# 03_MAIN_POWER.net
KiCad netlist of a schematic drawn in Altium Designer
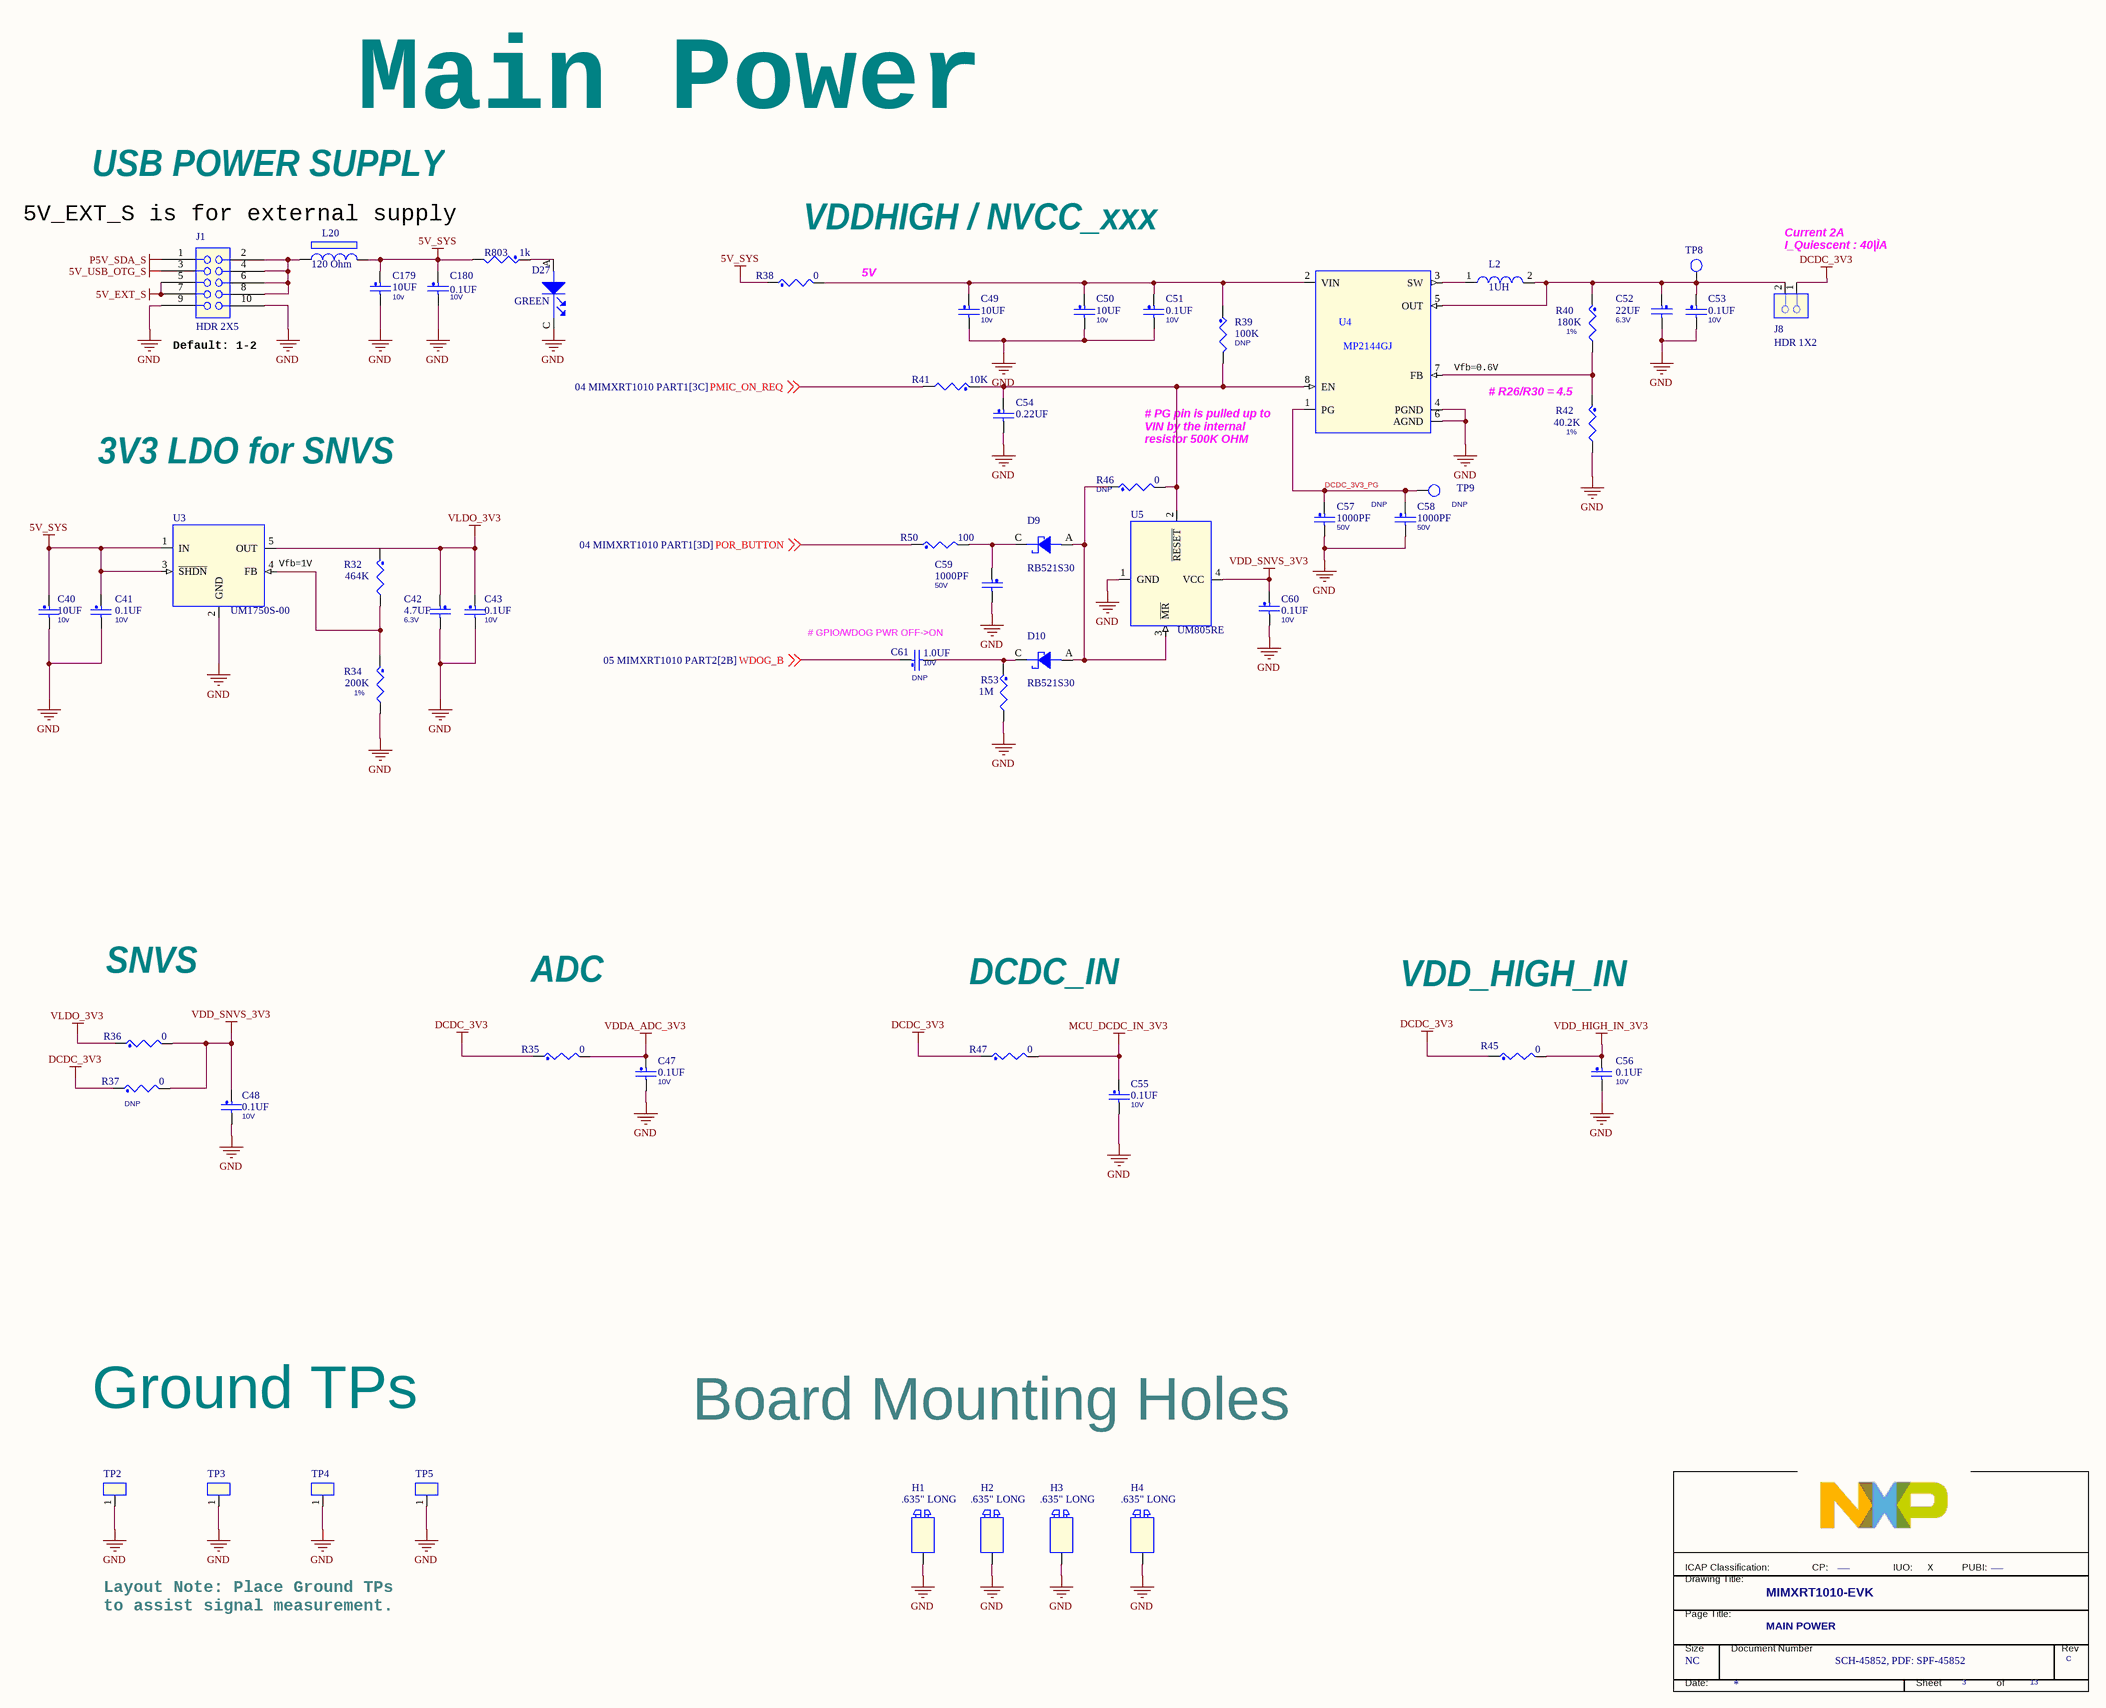
[diagram p0: 03 MAIN POWER.SchDoc]

(export (version "E")
  (design (tool "Eeschema 10.0.6"))
  (components
    (comp (ref "C40")
      (value "10UF")
      (footprint "CC0603_OV")
      (description "CAP CER 10UF 10V 10% X5R 0603")
      (fields (field (name "VOLTAGE") "10v") (field (name "TOLERANCE") "10%"))
      (libsource (lib "*") (part "CAP_NP"))
    )
    (comp (ref "C41")
      (value "0.1UF")
      (footprint "CC0402_25")
      (description "CAP CER 0.1UF 10V 10% X5R 0402")
      (fields (field (name "VOLTAGE") "10V") (field (name "TOLERANCE") "10%"))
      (libsource (lib "*") (part "CAP_NP"))
    )
    (comp (ref "C42")
      (value "4.7UF")
      (footprint "0402_CC")
      (description "CAP CER 4.7UF 6.3V 20% X5R 0402")
      (fields
        (field (name "TOLERANCE") "20%")
        (field (name "VOLTAGE RATING") "6.3V")
        (field (name "VOLTAGE") "6.3V")
      )
      (libsource (lib "*") (part "CAP_NP"))
    )
    (comp (ref "C43")
      (value "0.1UF")
      (footprint "CC0402_25")
      (description "CAP CER 0.1UF 10V 10% X5R 0402")
      (fields (field (name "VOLTAGE") "10V") (field (name "TOLERANCE") "10%"))
      (libsource (lib "*") (part "CAP_NP"))
    )
    (comp (ref "C47")
      (value "0.1UF")
      (footprint "CC0402_25")
      (description "CAP CER 0.1UF 10V 10% X5R 0402")
      (fields (field (name "VOLTAGE") "10V") (field (name "TOLERANCE") "10%"))
      (libsource (lib "*") (part "CAP_NP"))
    )
    (comp (ref "C48")
      (value "0.1UF")
      (footprint "CC0402_25")
      (description "CAP CER 0.1UF 10V 10% X5R 0402")
      (fields (field (name "VOLTAGE") "10V") (field (name "TOLERANCE") "10%"))
      (libsource (lib "*") (part "CAP_NP"))
    )
    (comp (ref "C49")
      (value "10UF")
      (footprint "CC0603_OV")
      (description "CAP CER 10UF 10V 10% X5R 0603")
      (fields (field (name "VOLTAGE") "10v") (field (name "TOLERANCE") "10%"))
      (libsource (lib "*") (part "CAP_NP"))
    )
    (comp (ref "C50")
      (value "10UF")
      (footprint "CC0603_OV")
      (description "CAP CER 10UF 10V 10% X5R 0603")
      (fields (field (name "TOLERANCE") "10%") (field (name "VOLTAGE") "10v"))
      (libsource (lib "*") (part "CAP_NP"))
    )
    (comp (ref "C51")
      (value "0.1UF")
      (footprint "CC0402_25")
      (description "CAP CER 0.1UF 10V 10% X5R 0402")
      (fields (field (name "TOLERANCE") "10%") (field (name "VOLTAGE") "10V"))
      (libsource (lib "*") (part "CAP_NP"))
    )
    (comp (ref "C52")
      (value "22UF")
      (footprint "0603_CC")
      (description "CAP CER 22UF 6.3V 20% X5R 0603")
      (fields
        (field (name "VOLTAGE RATING") "6.3V")
        (field (name "TOLERANCE") "20%")
        (field (name "VOLTAGE") "6.3V")
      )
      (libsource (lib "*") (part "CAP_NP"))
    )
    (comp (ref "C53")
      (value "0.1UF")
      (footprint "CC0402_25")
      (description "CAP CER 0.1UF 10V 10% X5R 0402")
      (fields (field (name "TOLERANCE") "10%") (field (name "VOLTAGE") "10V"))
      (libsource (lib "*") (part "CAP_NP"))
    )
    (comp (ref "C54")
      (value "0.22UF")
      (footprint "0402_CC")
      (description "CAP CER 0.22UF 6.3V 20% X5R 0402")
      (fields (field (name "TOLERANCE") "20%") (field (name "VOLTAGE") "6.3V"))
      (libsource (lib "*") (part "CAP_NP"))
    )
    (comp (ref "C55")
      (value "0.1UF")
      (footprint "CC0402_25")
      (description "CAP CER 0.1UF 10V 10% X5R 0402")
      (fields (field (name "VOLTAGE") "10V") (field (name "TOLERANCE") "10%"))
      (libsource (lib "*") (part "CAP_NP"))
    )
    (comp (ref "C56")
      (value "0.1UF")
      (footprint "CC0402_25")
      (description "CAP CER 0.1UF 10V 10% X5R 0402")
      (fields (field (name "VOLTAGE") "10V") (field (name "TOLERANCE") "10%"))
      (libsource (lib "*") (part "CAP_NP"))
    )
    (comp (ref "C57")
      (value "1000PF")
      (footprint "0402_CC")
      (description "CAP CER 1000PF 50V 5% C0G 0402")
      (fields (field (name "ASSY_OPT") "DNP") (field (name "VOLTAGE") "50V") (field (name "TOLERANCE") "5%"))
      (libsource (lib "*") (part "CAP_NP"))
    )
    (comp (ref "C58")
      (value "1000PF")
      (footprint "0402_CC")
      (description "CAP CER 1000PF 50V 5% C0G 0402")
      (fields (field (name "ASSY_OPT") "DNP") (field (name "TOLERANCE") "5%") (field (name "VOLTAGE") "50V"))
      (libsource (lib "*") (part "CAP_NP"))
    )
    (comp (ref "C59")
      (value "1000PF")
      (footprint "0402_CC")
      (description "CAP CER 1000PF 50V 5% C0G 0402")
      (fields (field (name "TOLERANCE") "5%") (field (name "VOLTAGE") "50V"))
      (libsource (lib "*") (part "CAP_NP"))
    )
    (comp (ref "C60")
      (value "0.1UF")
      (footprint "CC0402_25")
      (description "CAP CER 0.1UF 10V 10% X5R 0402")
      (fields (field (name "TOLERANCE") "10%") (field (name "VOLTAGE") "10V"))
      (libsource (lib "*") (part "CAP_NP"))
    )
    (comp (ref "C61")
      (value "1.0UF")
      (footprint "0402_cc")
      (description "CAP CER 1.0UF 10V 10% X5R 0402")
      (fields (field (name "ASSY_OPT") "DNP") (field (name "VOLTAGE") "10V"))
      (libsource (lib "*") (part "CAP_NP"))
    )
    (comp (ref "C179")
      (value "10UF")
      (footprint "CC0603_OV")
      (description "CAP CER 10UF 10V 10% X5R 0603")
      (fields (field (name "TOLERANCE") "10%") (field (name "VOLTAGE") "10v"))
      (libsource (lib "*") (part "CAP_NP"))
    )
    (comp (ref "C180")
      (value "0.1UF")
      (footprint "CC0402_25")
      (description "CAP CER 0.1UF 10V 10% X5R 0402")
      (fields (field (name "TOLERANCE") "10%") (field (name "VOLTAGE") "10V"))
      (libsource (lib "*") (part "CAP_NP"))
    )
    (comp (ref "D9")
      (value "RB521S30")
      (footprint "SOD523")
      (description "DIODE SCH RECT 200MA 30V AEC-Q101 SOD-523")
      (libsource (lib "*") (part "DIODE_SCHTKY"))
    )
    (comp (ref "D10")
      (value "RB521S30")
      (footprint "SOD523")
      (description "DIODE SCH RECT 200MA 30V AEC-Q101 SOD-523")
      (libsource (lib "*") (part "DIODE_SCHTKY"))
    )
    (comp (ref "D27")
      (value "GREEN")
      (footprint "LED_0603")
      (description "LED GRN SGL 25MA 0603")
      (libsource (lib "*") (part "LED"))
    )
    (comp (ref "H1")
      (value ".635\" LONG")
      (footprint "spacer_139t")
      (description "FASTENER, STANDOFF 4.5MMX3.53XM3.0X0.5 ROUND THR .635\"L BRASS")
      (libsource (lib "*") (part "SPACER"))
    )
    (comp (ref "H2")
      (value ".635\" LONG")
      (footprint "spacer_139t")
      (description "FASTENER, STANDOFF 4.5MMX3.53XM3.0X0.5 ROUND THR .635\"L BRASS")
      (libsource (lib "*") (part "SPACER"))
    )
    (comp (ref "H3")
      (value ".635\" LONG")
      (footprint "spacer_139t")
      (description "FASTENER, STANDOFF 4.5MMX3.53XM3.0X0.5 ROUND THR .635\"L BRASS")
      (libsource (lib "*") (part "SPACER"))
    )
    (comp (ref "H4")
      (value ".635\" LONG")
      (footprint "spacer_139t")
      (description "FASTENER, STANDOFF 4.5MMX3.53XM3.0X0.5 ROUND THR .635\"L BRASS")
      (libsource (lib "*") (part "SPACER"))
    )
    (comp (ref "J1")
      (value "HDR 2X5")
      (footprint "hdr205")
      (description "HDR 2X5 TH 100MIL CTR 338H AU 98L")
      (libsource (lib "*") (part "CONN_HDR_5X2"))
    )
    (comp (ref "J8")
      (value "HDR 1X2")
      (footprint "HDR102")
      (description "HDR 1X2 TH 100MIL SP 339H AU 98L")
      (libsource (lib "*") (part "CONN_HDR_2X1"))
    )
    (comp (ref "L2")
      (value "1UH")
      (footprint "ind_4020")
      (description "IND PWR 1UH@100KHZ 2.6A 30% SMT")
      (fields (field (name "TOLERANCE") "30%"))
      (libsource (lib "*") (part "IND"))
    )
    (comp (ref "L20")
      (value "120 Ohm")
      (footprint "0402_CC")
      (description "IND FER BEAD 120 OHM@100MHZ 0.5A 25% 0402")
      (fields (field (name "TOLERANCE") "25%"))
      (libsource (lib "*") (part "INDUCTOR_FERRITE"))
    )
    (comp (ref "R32")
      (value "464K")
      (footprint "0402_CC")
      (description "RES MF 464K 1/10W 1% AEC-Q200 0402")
      (fields (field (name "TOLERANCE") "1%"))
      (libsource (lib "*") (part "RES_Dup1"))
    )
    (comp (ref "R34")
      (value "200K")
      (footprint "0402_CC")
      (description "RES MF 200K 1/10W 1% AEC-Q200 0402")
      (fields (field (name "TOLERANCE") "1%"))
      (libsource (lib "*") (part "RES_Dup1"))
    )
    (comp (ref "R35")
      (value "0")
      (footprint "0402_CC")
      (description "RES MF ZERO OHM 1/16W 5% 0402")
      (fields (field (name "TOLERANCE") "5%"))
      (libsource (lib "*") (part "RES_Dup1"))
    )
    (comp (ref "R36")
      (value "0")
      (footprint "0402_CC")
      (description "RES MF ZERO OHM 1/16W 5% 0402")
      (fields (field (name "TOLERANCE") "5%"))
      (libsource (lib "*") (part "RES_Dup1"))
    )
    (comp (ref "R37")
      (value "0")
      (footprint "0402_CC")
      (description "RES MF ZERO OHM 1/16W 5% 0402")
      (fields (field (name "TOLERANCE") "5%") (field (name "ASSY_OPT") "DNP"))
      (libsource (lib "*") (part "RES_Dup1"))
    )
    (comp (ref "R38")
      (value "0")
      (footprint "0402_CC")
      (description "RES MF ZERO OHM 1/16W 5% 0402")
      (fields (field (name "TOLERANCE") "5%"))
      (libsource (lib "*") (part "RES_Dup1"))
    )
    (comp (ref "R39")
      (value "100K")
      (footprint "0402_CC")
      (description "RES MF 100K 1/16W 5% 0402")
      (fields (field (name "ASSY_OPT") "DNP") (field (name "TOLERANCE") "5%"))
      (libsource (lib "*") (part "RES_Dup1"))
    )
    (comp (ref "R40")
      (value "180K")
      (footprint "0402_CC")
      (description "RES MF 180K 1/10W 1% AEC-Q200 0402")
      (fields (field (name "TOLERANCE") "1%"))
      (libsource (lib "*") (part "RES_Dup1"))
    )
    (comp (ref "R41")
      (value "10K")
      (footprint "0402_CC")
      (description "RES MF 10K 1/16W 5% 0402")
      (fields (field (name "TOLERANCE") "5%"))
      (libsource (lib "*") (part "RES_Dup1"))
    )
    (comp (ref "R42")
      (value "40.2K")
      (footprint "0402_CC")
      (description "RES MF 40.2K  1/16W 1% 0402")
      (fields (field (name "TOLERANCE") "1%"))
      (libsource (lib "*") (part "RES_Dup1"))
    )
    (comp (ref "R45")
      (value "0")
      (footprint "0402_CC")
      (description "RES MF ZERO OHM 1/16W 5% 0402")
      (fields (field (name "TOLERANCE") "5%"))
      (libsource (lib "*") (part "RES_Dup1"))
    )
    (comp (ref "R46")
      (value "0")
      (footprint "0402_CC")
      (description "RES MF ZERO OHM 1/16W 5% 0402")
      (fields (field (name "TOLERANCE") "5%") (field (name "ASSY_OPT") "DNP"))
      (libsource (lib "*") (part "RES_Dup1"))
    )
    (comp (ref "R47")
      (value "0")
      (footprint "0402_CC")
      (description "RES MF ZERO OHM 1/16W 5% 0402")
      (fields (field (name "TOLERANCE") "5%"))
      (libsource (lib "*") (part "RES_Dup1"))
    )
    (comp (ref "R50")
      (value "100")
      (footprint "0402_CC")
      (description "RES MF 100 OHM 1/16W 1% 0402")
      (fields (field (name "TOLERANCE") "1%"))
      (libsource (lib "*") (part "RES_Dup1"))
    )
    (comp (ref "R53")
      (value "1M")
      (footprint "0402_CC")
      (description "RES MF 1M 1/10W 5% AEC-Q200 0402")
      (fields (field (name "TOLERANCE") "5%"))
      (libsource (lib "*") (part "RES_Dup1"))
    )
    (comp (ref "R803")
      (value "1k")
      (footprint "0402_CC")
      (description "RES MF 1.0K 1/16W 5% 0402")
      (fields (field (name "TOLERANCE") "5%"))
      (libsource (lib "*") (part "RES_Dup1"))
    )
    (comp (ref "TP2")
      (value "5006")
      (footprint "tp_th_063")
      (description "TEST POINT BLK 70X220 MIL TH")
      (libsource (lib "*") (part "TEST_POINT"))
    )
    (comp (ref "TP3")
      (value "5006")
      (footprint "tp_th_063")
      (description "TEST POINT BLK 70X220 MIL TH")
      (libsource (lib "*") (part "TEST_POINT"))
    )
    (comp (ref "TP4")
      (value "5006")
      (footprint "tp_th_063")
      (description "TEST POINT BLK 70X220 MIL TH")
      (libsource (lib "*") (part "TEST_POINT"))
    )
    (comp (ref "TP5")
      (value "5006")
      (footprint "tp_th_063")
      (description "TEST POINT BLK 70X220 MIL TH")
      (libsource (lib "*") (part "TEST_POINT"))
    )
    (comp (ref "TP8")
      (value "TP_35MIL")
      (footprint "testpoint_35mil")
      (description "TEST POINT PAD .035 SMT, no part to order")
      (libsource (lib "*") (part "T POINT R"))
    )
    (comp (ref "TP9")
      (value "TP_35MIL")
      (footprint "testpoint_35mil")
      (description "TEST POINT PAD .035 SMT, no part to order")
      (libsource (lib "*") (part "T POINT R"))
    )
    (comp (ref "U3")
      (value "UM1750S-00")
      (footprint "sot23-5_a")
      (description "IC VREG LDO ADJ 1-5V 350mA 2.5-6V SOT23-5")
      (libsource (lib "*") (part "UM1750S-00_5P"))
    )
    (comp (ref "U4")
      (value "MP2144GJ")
      (footprint "tsot23_8_0p65_2x1")
      (description "IC SYNC STEP-DOWN SW 1.2MHZ 0.6V 2A 2.5-5.5V TSOT23-8")
      (libsource (lib "*") (part "MP2144GJ_TSOT23_8P"))
    )
    (comp (ref "U5")
      (value "UM805RE")
      (footprint "sot_143")
      (description "IC VOLT MONITOR 2.63V VTH RST 1-5.5V SOT143")
      (libsource (lib "*") (part "UM805_4P"))
    )
  )
  (nets
    (net (code "1") (name "/DCDC_3V3_PG") (class "Default")
      (node (ref "C57") (pin "1") (pinfunction "1_1") (pintype "passive"))
      (node (ref "C58") (pin "1") (pinfunction "1_1") (pintype "passive"))
      (node (ref "TP9") (pin "1") (pinfunction "TP_1") (pintype "passive"))
      (node (ref "U4") (pin "1") (pinfunction "PG_1") (pintype "open_collector"))
    )
    (net (code "2") (name "5V_EXT_S") (class "Default")
      (node (ref "J1") (pin "5") (pinfunction "A3_5") (pintype "passive"))
      (node (ref "J1") (pin "7") (pinfunction "A4_7") (pintype "passive"))
    )
    (net (code "3") (name "5V_SYS") (class "Default")
      (node (ref "C179") (pin "1") (pinfunction "1_1") (pintype "passive"))
      (node (ref "C180") (pin "1") (pinfunction "1_1") (pintype "passive"))
      (node (ref "C40") (pin "1") (pinfunction "1_1") (pintype "passive"))
      (node (ref "C41") (pin "1") (pinfunction "1_1") (pintype "passive"))
      (node (ref "L20") (pin "2") (pinfunction "2_2") (pintype "passive"))
      (node (ref "R38") (pin "1") (pinfunction "1_1") (pintype "passive"))
      (node (ref "R803") (pin "2") (pinfunction "2_2") (pintype "passive"))
      (node (ref "U3") (pin "1") (pinfunction "IN_1") (pintype "power_in"))
      (node (ref "U3") (pin "3") (pinfunction "~{SHDN}_3") (pintype "input"))
    )
    (net (code "4") (name "5V_USB_OTG_S") (class "Default")
      (node (ref "J1") (pin "3") (pinfunction "A2_3") (pintype "passive"))
    )
    (net (code "5") (name "DCDC_3V3") (class "Default")
      (node (ref "J8") (pin "1") (pinfunction "1_1") (pintype "passive"))
      (node (ref "R35") (pin "1") (pinfunction "1_1") (pintype "passive"))
      (node (ref "R37") (pin "1") (pinfunction "1_1") (pintype "passive"))
      (node (ref "R45") (pin "1") (pinfunction "1_1") (pintype "passive"))
      (node (ref "R47") (pin "1") (pinfunction "1_1") (pintype "passive"))
    )
    (net (code "6") (name "GND") (class "Default")
      (node (ref "C179") (pin "2") (pinfunction "2_2") (pintype "passive"))
      (node (ref "C180") (pin "2") (pinfunction "2_2") (pintype "passive"))
      (node (ref "C40") (pin "2") (pinfunction "2_2") (pintype "passive"))
      (node (ref "C41") (pin "2") (pinfunction "2_2") (pintype "passive"))
      (node (ref "C42") (pin "2") (pinfunction "2_2") (pintype "passive"))
      (node (ref "C43") (pin "2") (pinfunction "2_2") (pintype "passive"))
      (node (ref "C47") (pin "2") (pinfunction "2_2") (pintype "passive"))
      (node (ref "C48") (pin "2") (pinfunction "2_2") (pintype "passive"))
      (node (ref "C49") (pin "2") (pinfunction "2_2") (pintype "passive"))
      (node (ref "C50") (pin "2") (pinfunction "2_2") (pintype "passive"))
      (node (ref "C51") (pin "2") (pinfunction "2_2") (pintype "passive"))
      (node (ref "C52") (pin "2") (pinfunction "2_2") (pintype "passive"))
      (node (ref "C53") (pin "2") (pinfunction "2_2") (pintype "passive"))
      (node (ref "C54") (pin "2") (pinfunction "2_2") (pintype "passive"))
      (node (ref "C55") (pin "2") (pinfunction "2_2") (pintype "passive"))
      (node (ref "C56") (pin "2") (pinfunction "2_2") (pintype "passive"))
      (node (ref "C57") (pin "2") (pinfunction "2_2") (pintype "passive"))
      (node (ref "C58") (pin "2") (pinfunction "2_2") (pintype "passive"))
      (node (ref "C59") (pin "2") (pinfunction "2_2") (pintype "passive"))
      (node (ref "C60") (pin "2") (pinfunction "2_2") (pintype "passive"))
      (node (ref "D27") (pin "C") (pinfunction "CATHODE_C") (pintype "passive"))
      (node (ref "H1") (pin "1") (pinfunction "NC_1_1") (pintype "passive"))
      (node (ref "H2") (pin "1") (pinfunction "NC_1_1") (pintype "passive"))
      (node (ref "H3") (pin "1") (pinfunction "NC_1_1") (pintype "passive"))
      (node (ref "H4") (pin "1") (pinfunction "NC_1_1") (pintype "passive"))
      (node (ref "J1") (pin "10") (pinfunction "B5_10") (pintype "passive"))
      (node (ref "J1") (pin "9") (pinfunction "A5_9") (pintype "passive"))
      (node (ref "R34") (pin "2") (pinfunction "2_2") (pintype "passive"))
      (node (ref "R42") (pin "2") (pinfunction "2_2") (pintype "passive"))
      (node (ref "R53") (pin "2") (pinfunction "2_2") (pintype "passive"))
      (node (ref "TP2") (pin "1") (pinfunction "1_1") (pintype "passive"))
      (node (ref "TP3") (pin "1") (pinfunction "1_1") (pintype "passive"))
      (node (ref "TP4") (pin "1") (pinfunction "1_1") (pintype "passive"))
      (node (ref "TP5") (pin "1") (pinfunction "1_1") (pintype "passive"))
      (node (ref "U3") (pin "2") (pinfunction "GND_2") (pintype "power_in"))
      (node (ref "U4") (pin "4") (pinfunction "PGND_4") (pintype "power_in"))
      (node (ref "U4") (pin "6") (pinfunction "AGND_6") (pintype "power_in"))
      (node (ref "U5") (pin "1") (pinfunction "GND_1") (pintype "power_in"))
    )
    (net (code "7") (name "MCU_DCDC_IN_3V3") (class "Default")
      (node (ref "C55") (pin "1") (pinfunction "1_1") (pintype "passive"))
      (node (ref "R47") (pin "2") (pinfunction "2_2") (pintype "passive"))
    )
    (net (code "8") (name "Net-(C59-Pad1)") (class "Default")
      (node (ref "C59") (pin "1") (pinfunction "1_1") (pintype "passive"))
      (node (ref "D9") (pin "C") (pinfunction "C_C") (pintype "passive"))
      (node (ref "R50") (pin "2") (pinfunction "2_2") (pintype "passive"))
    )
    (net (code "9") (name "Net-(C61-Pad2)") (class "Default")
      (node (ref "C61") (pin "2") (pinfunction "2_2") (pintype "passive"))
      (node (ref "D10") (pin "C") (pinfunction "C_C") (pintype "passive"))
      (node (ref "R53") (pin "1") (pinfunction "1_1") (pintype "passive"))
    )
    (net (code "10") (name "Net-(D27-ANODE)") (class "Default")
      (node (ref "D27") (pin "A") (pinfunction "ANODE_A") (pintype "passive"))
      (node (ref "R803") (pin "1") (pinfunction "1_1") (pintype "passive"))
    )
    (net (code "11") (name "Net-(J1-B1)") (class "Default")
      (node (ref "J1") (pin "2") (pinfunction "B1_2") (pintype "passive"))
      (node (ref "J1") (pin "4") (pinfunction "B2_4") (pintype "passive"))
      (node (ref "J1") (pin "6") (pinfunction "B3_6") (pintype "passive"))
      (node (ref "J1") (pin "8") (pinfunction "B4_8") (pintype "passive"))
      (node (ref "L20") (pin "1") (pinfunction "1_1") (pintype "passive"))
    )
    (net (code "12") (name "Net-(TP8-TP)") (class "Default")
      (node (ref "C52") (pin "1") (pinfunction "1_1") (pintype "passive"))
      (node (ref "C53") (pin "1") (pinfunction "1_1") (pintype "passive"))
      (node (ref "J8") (pin "2") (pinfunction "2_2") (pintype "passive"))
      (node (ref "L2") (pin "2") (pinfunction "2_2") (pintype "passive"))
      (node (ref "R40") (pin "1") (pinfunction "1_1") (pintype "passive"))
      (node (ref "TP8") (pin "1") (pinfunction "TP_1") (pintype "passive"))
      (node (ref "U4") (pin "5") (pinfunction "OUT_5") (pintype "input"))
    )
    (net (code "13") (name "Net-(U3-FB)") (class "Default")
      (node (ref "R32") (pin "2") (pinfunction "2_2") (pintype "passive"))
      (node (ref "R34") (pin "1") (pinfunction "1_1") (pintype "passive"))
      (node (ref "U3") (pin "4") (pinfunction "FB_4") (pintype "input"))
    )
    (net (code "14") (name "Net-(U4-EN)") (class "Default")
      (node (ref "C54") (pin "1") (pinfunction "1_1") (pintype "passive"))
      (node (ref "R39") (pin "2") (pinfunction "2_2") (pintype "passive"))
      (node (ref "R41") (pin "1") (pinfunction "1_1") (pintype "passive"))
      (node (ref "R46") (pin "2") (pinfunction "2_2") (pintype "passive"))
      (node (ref "U4") (pin "8") (pinfunction "EN_8") (pintype "input"))
      (node (ref "U5") (pin "2") (pinfunction "~{RESET}_2") (pintype "open_collector"))
    )
    (net (code "15") (name "Net-(U4-FB)") (class "Default")
      (node (ref "R40") (pin "2") (pinfunction "2_2") (pintype "passive"))
      (node (ref "R42") (pin "1") (pinfunction "1_1") (pintype "passive"))
      (node (ref "U4") (pin "7") (pinfunction "FB_7") (pintype "input"))
    )
    (net (code "16") (name "Net-(U4-SW)") (class "Default")
      (node (ref "L2") (pin "1") (pinfunction "1_1") (pintype "passive"))
      (node (ref "U4") (pin "3") (pinfunction "SW_3") (pintype "output"))
    )
    (net (code "17") (name "Net-(U4-VIN)") (class "Default")
      (node (ref "C49") (pin "1") (pinfunction "1_1") (pintype "passive"))
      (node (ref "C50") (pin "1") (pinfunction "1_1") (pintype "passive"))
      (node (ref "C51") (pin "1") (pinfunction "1_1") (pintype "passive"))
      (node (ref "R38") (pin "2") (pinfunction "2_2") (pintype "passive"))
      (node (ref "R39") (pin "1") (pinfunction "1_1") (pintype "passive"))
      (node (ref "U4") (pin "2") (pinfunction "VIN_2") (pintype "power_in"))
    )
    (net (code "18") (name "Net-(U5-~{MR})") (class "Default")
      (node (ref "D10") (pin "A") (pinfunction "A_A") (pintype "passive"))
      (node (ref "D9") (pin "A") (pinfunction "A_A") (pintype "passive"))
      (node (ref "R46") (pin "1") (pinfunction "1_1") (pintype "passive"))
      (node (ref "U5") (pin "3") (pinfunction "~{MR}_3") (pintype "input"))
    )
    (net (code "19") (name "P5V_SDA_S") (class "Default")
      (node (ref "J1") (pin "1") (pinfunction "A1_1") (pintype "passive"))
    )
    (net (code "20") (name "PMIC_ON_REQ") (class "Default")
      (node (ref "R41") (pin "2") (pinfunction "2_2") (pintype "passive"))
    )
    (net (code "21") (name "POR_BUTTON") (class "Default")
      (node (ref "R50") (pin "1") (pinfunction "1_1") (pintype "passive"))
    )
    (net (code "22") (name "VDDA_ADC_3V3") (class "Default")
      (node (ref "C47") (pin "1") (pinfunction "1_1") (pintype "passive"))
      (node (ref "R35") (pin "2") (pinfunction "2_2") (pintype "passive"))
    )
    (net (code "23") (name "VDD_HIGH_IN_3V3") (class "Default")
      (node (ref "C56") (pin "1") (pinfunction "1_1") (pintype "passive"))
      (node (ref "R45") (pin "2") (pinfunction "2_2") (pintype "passive"))
    )
    (net (code "24") (name "VDD_SNVS_3V3") (class "Default")
      (node (ref "C48") (pin "1") (pinfunction "1_1") (pintype "passive"))
      (node (ref "C60") (pin "1") (pinfunction "1_1") (pintype "passive"))
      (node (ref "R36") (pin "2") (pinfunction "2_2") (pintype "passive"))
      (node (ref "R37") (pin "2") (pinfunction "2_2") (pintype "passive"))
      (node (ref "U5") (pin "4") (pinfunction "VCC_4") (pintype "power_in"))
    )
    (net (code "25") (name "VLDO_3V3") (class "Default")
      (node (ref "C42") (pin "1") (pinfunction "1_1") (pintype "passive"))
      (node (ref "C43") (pin "1") (pinfunction "1_1") (pintype "passive"))
      (node (ref "R32") (pin "1") (pinfunction "1_1") (pintype "passive"))
      (node (ref "R36") (pin "1") (pinfunction "1_1") (pintype "passive"))
      (node (ref "U3") (pin "5") (pinfunction "OUT_5") (pintype "power_in"))
    )
    (net (code "26") (name "WDOG_B") (class "Default")
      (node (ref "C61") (pin "1") (pinfunction "1_1") (pintype "passive"))
    )
  )
)
